# abacusprojecteasyedav1_0.net
KiCad netlist of a schematic drawn in EasyEDA
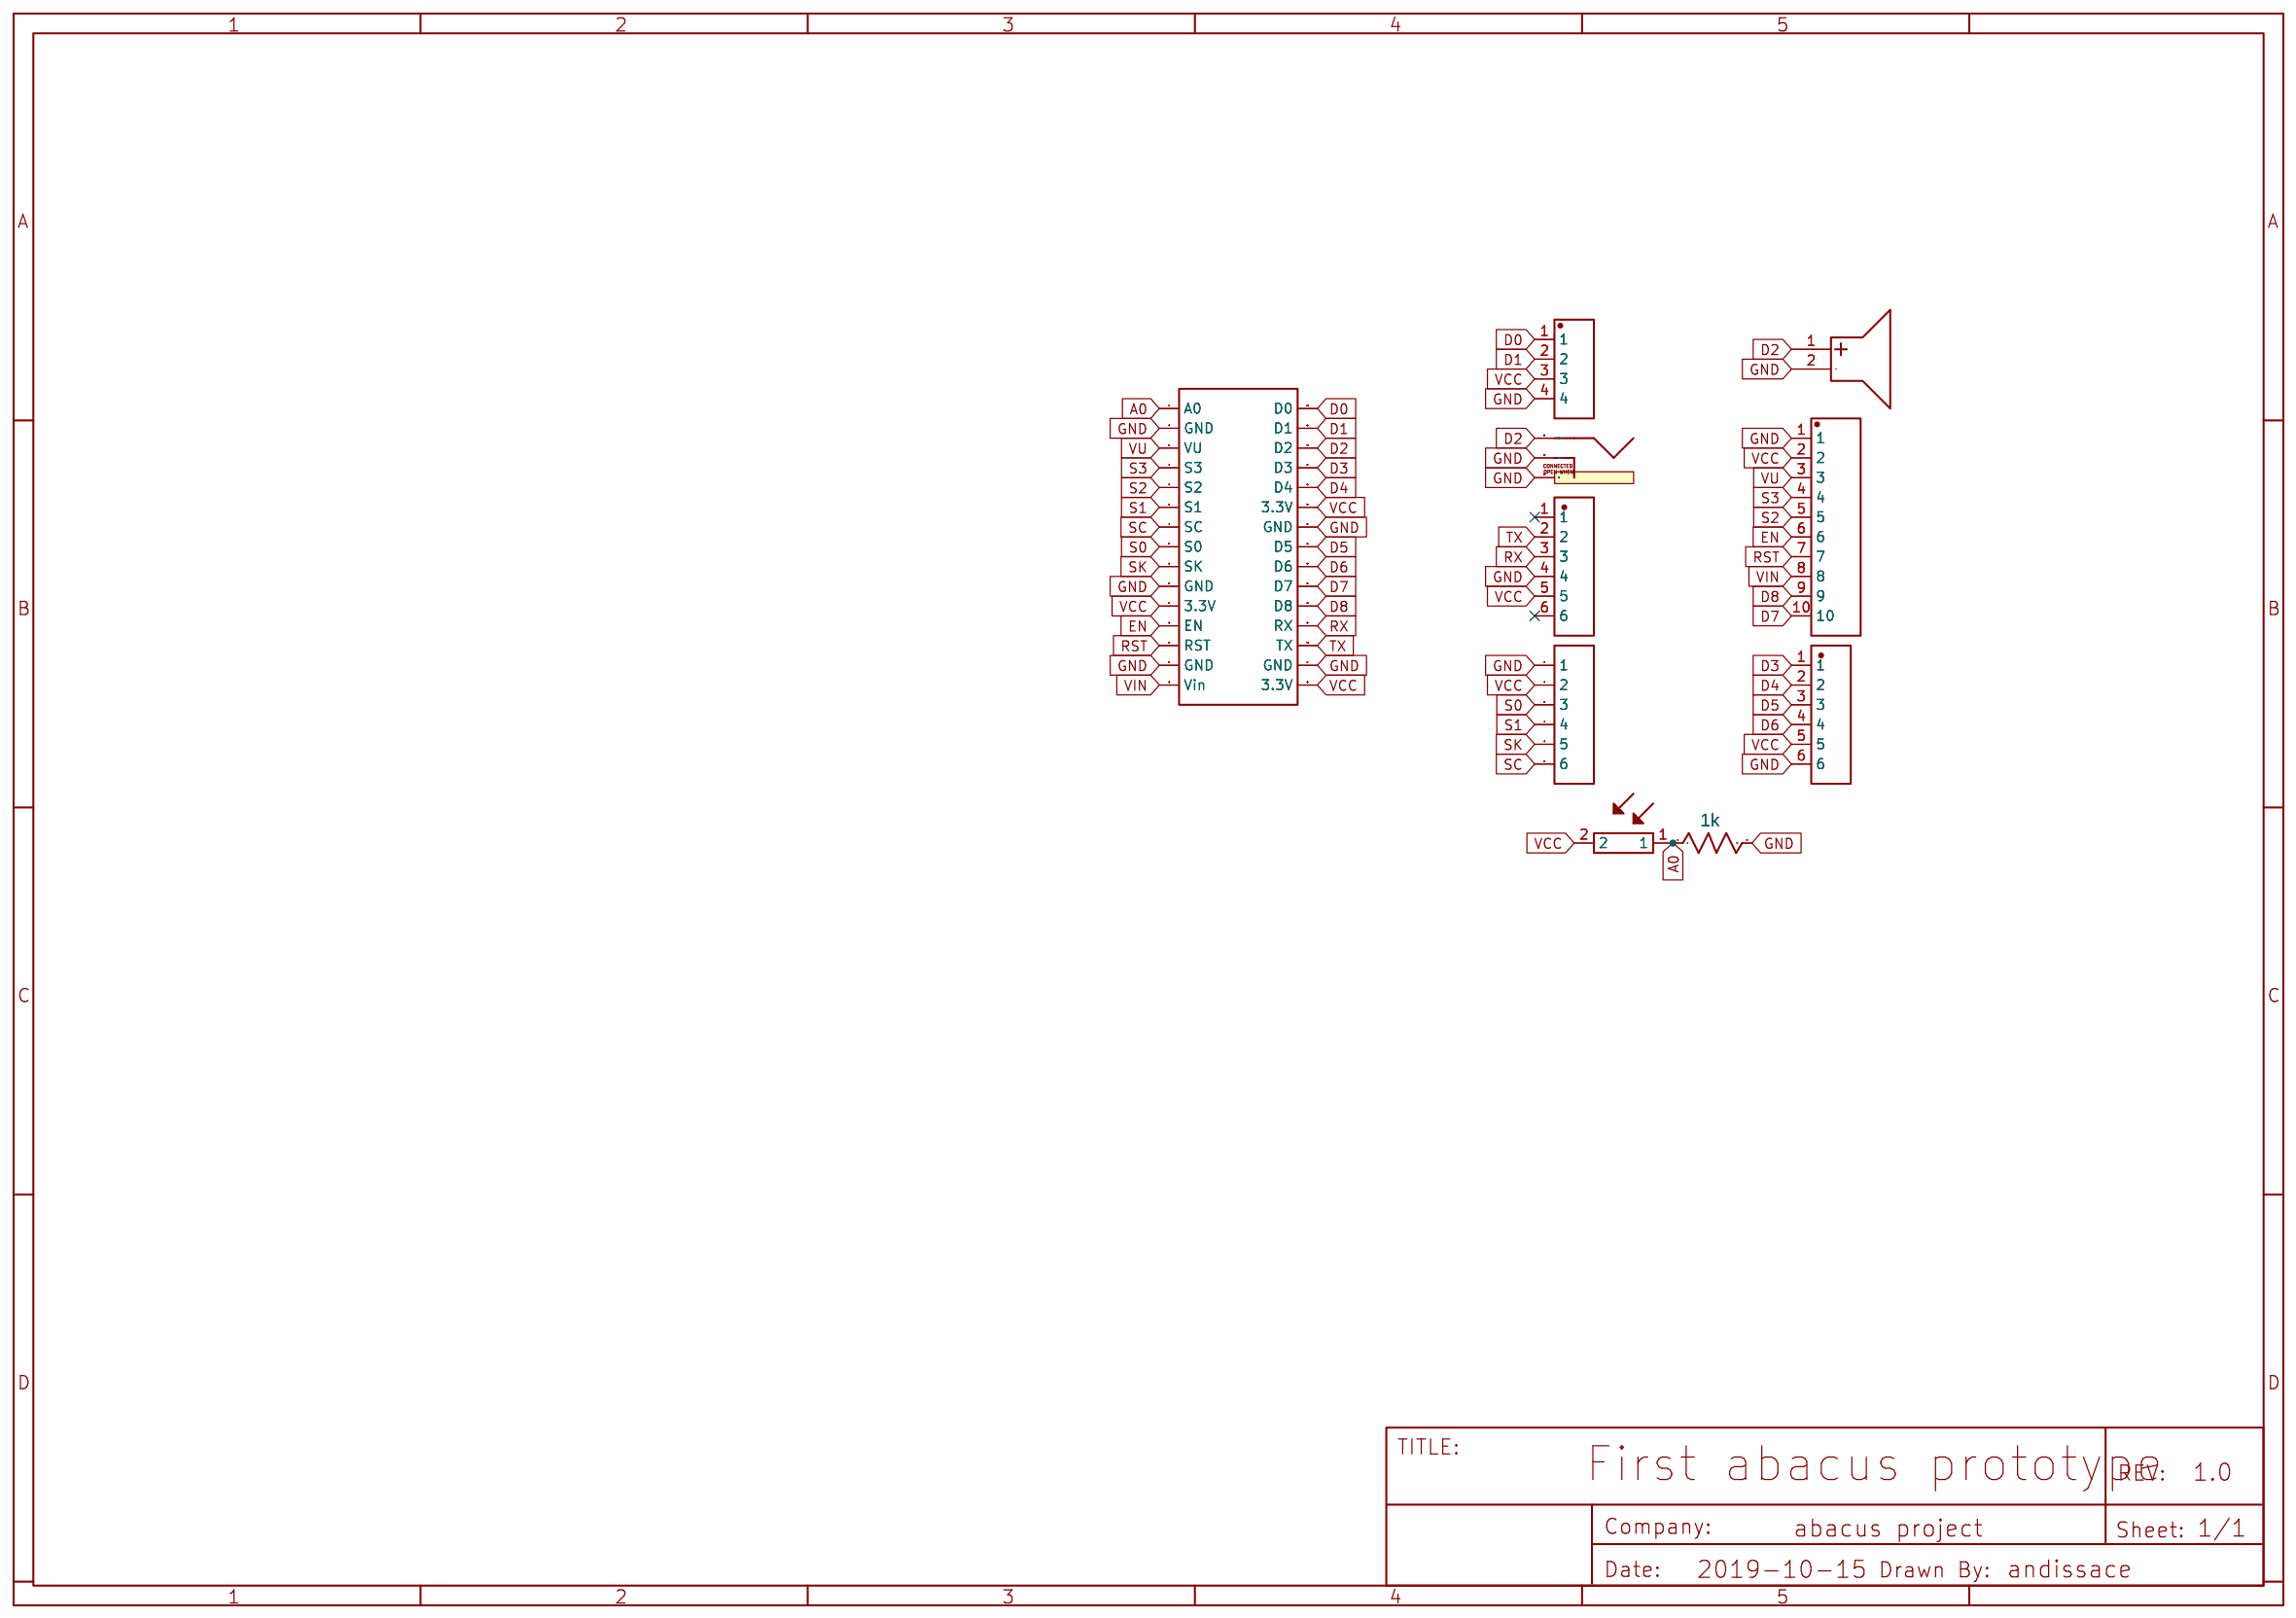
[diagram p0: schematic sheet]

(export (version "E")
  (design (tool "Eeschema 10.0.6"))
  (components
    (comp (ref "BUZZER1")
      (value "BL-PBZ12065C2705YA")
      (fields (field (name "BOM_Supplier Part") "C249440"))
      (libsource (lib "") (part "Unknown_930_180"))
    )
    (comp (ref "H1")
      (value "Header-Male-2.54_1x10")
      (fields
        (field (name "BOM_Manufacturer Part") "Headers  Pins2.54mm1*10P")
        (field (name "BOM_Supplier Part") "C57369")
      )
      (libsource (lib "") (part "Unknown_915_260"))
    )
    (comp (ref "H2")
      (value "Header-Male-2.54_1x4_C59481")
      (fields
        (field (name "BOM_Manufacturer Part") "Headers  Pins 1*4P")
        (field (name "BOM_Supplier Part") "C59481")
      )
      (libsource (lib "") (part "Unknown_785_180"))
    )
    (comp (ref "J1") (value "RCA") (libsource (lib "") (part "Unknown_780_225")))
    (comp (ref "P1")
      (value "Header-Female-2.54_1x6")
      (fields
        (field (name "BOM_Manufacturer Part") "Female header 1*6p")
        (field (name "BOM_Supplier Part") "C40877")
      )
      (libsource (lib "") (part "Unknown_785_355"))
    )
    (comp (ref "P2")
      (value "Header-Female-2.54_1x6")
      (fields
        (field (name "BOM_Manufacturer Part") "Female header 1*6p")
        (field (name "BOM_Supplier Part") "C40877")
      )
      (libsource (lib "") (part "Unknown_790_280"))
    )
    (comp (ref "P3")
      (value "Header-Female-2.54_1x6")
      (fields
        (field (name "BOM_Manufacturer Part") "Female header 1*6p")
        (field (name "BOM_Supplier Part") "C40877")
      )
      (libsource (lib "") (part "Unknown_920_355"))
    )
    (comp (ref "R1") (value "LDR") (libsource (lib "") (part "Unknown_810_415")))
    (comp (ref "R2") (value "1k") (libsource (lib "") (part "Res_AXIAL-0.3(1/8W)_US")))
    (comp (ref "U1")
      (value "NodeMcu_V3_LoLin")
      (fields (field (name "BOM_Manufacturer Part") "NodeMcu V3 LoLin"))
      (libsource (lib "") (part "Unknown_620_270"))
    )
  )
  (nets
    (net (code "1") (name "A0") (class "Default")
      (node (ref "R1") (pin "1") (pinfunction "1_1") (pintype "unspecified"))
      (node (ref "R2") (pin "1") (pinfunction "1_1") (pintype "unspecified"))
      (node (ref "U1") (pin "1") (pinfunction "A0_1") (pintype "unspecified"))
    )
    (net (code "2") (name "D0") (class "Default")
      (node (ref "H2") (pin "1") (pinfunction "1_1") (pintype "unspecified"))
      (node (ref "U1") (pin "30") (pinfunction "D0_30") (pintype "unspecified"))
    )
    (net (code "3") (name "D1") (class "Default")
      (node (ref "H2") (pin "2") (pinfunction "2_2") (pintype "unspecified"))
      (node (ref "U1") (pin "29") (pinfunction "D1_29") (pintype "unspecified"))
    )
    (net (code "4") (name "D2") (class "Default")
      (node (ref "BUZZER1") (pin "1") (pinfunction "+_1") (pintype "unspecified"))
      (node (ref "J1") (pin "SHELL") (pinfunction "SHELL_SHELL") (pintype "bidirectional"))
      (node (ref "U1") (pin "28") (pinfunction "D2_28") (pintype "unspecified"))
    )
    (net (code "5") (name "D3") (class "Default")
      (node (ref "P3") (pin "1") (pinfunction "1_1") (pintype "unspecified"))
      (node (ref "U1") (pin "27") (pinfunction "D3_27") (pintype "unspecified"))
    )
    (net (code "6") (name "D4") (class "Default")
      (node (ref "P3") (pin "2") (pinfunction "2_2") (pintype "unspecified"))
      (node (ref "U1") (pin "26") (pinfunction "D4_26") (pintype "unspecified"))
    )
    (net (code "7") (name "D5") (class "Default")
      (node (ref "P3") (pin "3") (pinfunction "3_3") (pintype "unspecified"))
      (node (ref "U1") (pin "23") (pinfunction "D5_23") (pintype "unspecified"))
    )
    (net (code "8") (name "D6") (class "Default")
      (node (ref "P3") (pin "4") (pinfunction "4_4") (pintype "unspecified"))
      (node (ref "U1") (pin "22") (pinfunction "D6_22") (pintype "unspecified"))
    )
    (net (code "9") (name "D7") (class "Default")
      (node (ref "H1") (pin "10") (pinfunction "10_10") (pintype "unspecified"))
      (node (ref "U1") (pin "21") (pinfunction "D7_21") (pintype "unspecified"))
    )
    (net (code "10") (name "D8") (class "Default")
      (node (ref "H1") (pin "9") (pinfunction "9_9") (pintype "unspecified"))
      (node (ref "U1") (pin "20") (pinfunction "D8_20") (pintype "unspecified"))
    )
    (net (code "11") (name "EN") (class "Default")
      (node (ref "H1") (pin "6") (pinfunction "6_6") (pintype "unspecified"))
      (node (ref "U1") (pin "12") (pinfunction "EN_12") (pintype "unspecified"))
    )
    (net (code "12") (name "GND") (class "Default")
      (node (ref "BUZZER1") (pin "2") (pinfunction "-_2") (pintype "unspecified"))
      (node (ref "H1") (pin "1") (pinfunction "1_1") (pintype "unspecified"))
      (node (ref "H2") (pin "4") (pinfunction "4_4") (pintype "unspecified"))
      (node (ref "J1") (pin "PIN") (pinfunction "PIN_PIN") (pintype "bidirectional"))
      (node (ref "J1") (pin "SWITCH") (pinfunction "SWITCH_SWITCH") (pintype "bidirectional"))
      (node (ref "P1") (pin "1") (pinfunction "1_1") (pintype "input"))
      (node (ref "P2") (pin "4") (pinfunction "4_4") (pintype "unspecified"))
      (node (ref "P3") (pin "6") (pinfunction "6_6") (pintype "unspecified"))
      (node (ref "R2") (pin "2") (pinfunction "2_2") (pintype "unspecified"))
      (node (ref "U1") (pin "10") (pinfunction "GND_10") (pintype "unspecified"))
      (node (ref "U1") (pin "14") (pinfunction "GND_14") (pintype "unspecified"))
      (node (ref "U1") (pin "17") (pinfunction "GND_17") (pintype "unspecified"))
      (node (ref "U1") (pin "2") (pinfunction "GND_2") (pintype "unspecified"))
      (node (ref "U1") (pin "24") (pinfunction "GND_24") (pintype "unspecified"))
    )
    (net (code "13") (name "RST") (class "Default")
      (node (ref "H1") (pin "7") (pinfunction "7_7") (pintype "unspecified"))
      (node (ref "U1") (pin "13") (pinfunction "RST_13") (pintype "unspecified"))
    )
    (net (code "14") (name "RX") (class "Default")
      (node (ref "P2") (pin "3") (pinfunction "3_3") (pintype "unspecified"))
      (node (ref "U1") (pin "19") (pinfunction "RX_19") (pintype "unspecified"))
    )
    (net (code "15") (name "S0") (class "Default")
      (node (ref "P1") (pin "3") (pinfunction "3_3") (pintype "input"))
      (node (ref "U1") (pin "8") (pinfunction "S0_8") (pintype "unspecified"))
    )
    (net (code "16") (name "S1") (class "Default")
      (node (ref "P1") (pin "4") (pinfunction "4_4") (pintype "input"))
      (node (ref "U1") (pin "6") (pinfunction "S1_6") (pintype "unspecified"))
    )
    (net (code "17") (name "S2") (class "Default")
      (node (ref "H1") (pin "5") (pinfunction "5_5") (pintype "unspecified"))
      (node (ref "U1") (pin "5") (pinfunction "S2_5") (pintype "unspecified"))
    )
    (net (code "18") (name "S3") (class "Default")
      (node (ref "H1") (pin "4") (pinfunction "4_4") (pintype "unspecified"))
      (node (ref "U1") (pin "4") (pinfunction "S3_4") (pintype "unspecified"))
    )
    (net (code "19") (name "SC") (class "Default")
      (node (ref "P1") (pin "6") (pinfunction "6_6") (pintype "input"))
      (node (ref "U1") (pin "7") (pinfunction "SC_7") (pintype "unspecified"))
    )
    (net (code "20") (name "SK") (class "Default")
      (node (ref "P1") (pin "5") (pinfunction "5_5") (pintype "input"))
      (node (ref "U1") (pin "9") (pinfunction "SK_9") (pintype "unspecified"))
    )
    (net (code "21") (name "TX") (class "Default")
      (node (ref "P2") (pin "2") (pinfunction "2_2") (pintype "unspecified"))
      (node (ref "U1") (pin "18") (pinfunction "TX_18") (pintype "unspecified"))
    )
    (net (code "22") (name "VCC") (class "Default")
      (node (ref "H1") (pin "2") (pinfunction "2_2") (pintype "unspecified"))
      (node (ref "H2") (pin "3") (pinfunction "3_3") (pintype "unspecified"))
      (node (ref "P1") (pin "2") (pinfunction "2_2") (pintype "input"))
      (node (ref "P2") (pin "5") (pinfunction "5_5") (pintype "unspecified"))
      (node (ref "P3") (pin "5") (pinfunction "5_5") (pintype "unspecified"))
      (node (ref "R1") (pin "2") (pinfunction "2_2") (pintype "unspecified"))
      (node (ref "U1") (pin "11") (pinfunction "3.3V_11") (pintype "unspecified"))
      (node (ref "U1") (pin "16") (pinfunction "3.3V_16") (pintype "unspecified"))
      (node (ref "U1") (pin "25") (pinfunction "3.3V_25") (pintype "unspecified"))
    )
    (net (code "23") (name "VIN") (class "Default")
      (node (ref "H1") (pin "8") (pinfunction "8_8") (pintype "unspecified"))
      (node (ref "U1") (pin "15") (pinfunction "Vin_15") (pintype "unspecified"))
    )
    (net (code "24") (name "VU") (class "Default")
      (node (ref "H1") (pin "3") (pinfunction "3_3") (pintype "unspecified"))
      (node (ref "U1") (pin "3") (pinfunction "VU_3") (pintype "unspecified"))
    )
    (net (code "25") (name "unconnected-(P2-Pad1)") (class "Default")
      (node (ref "P2") (pin "1") (pinfunction "1_1") (pintype "unspecified+no_connect"))
    )
    (net (code "26") (name "unconnected-(P2-Pad6)") (class "Default")
      (node (ref "P2") (pin "6") (pinfunction "6_6") (pintype "unspecified+no_connect"))
    )
  )
)
